# Startracker_Mainboard.net
KiCad netlist of a schematic drawn in Altium Designer
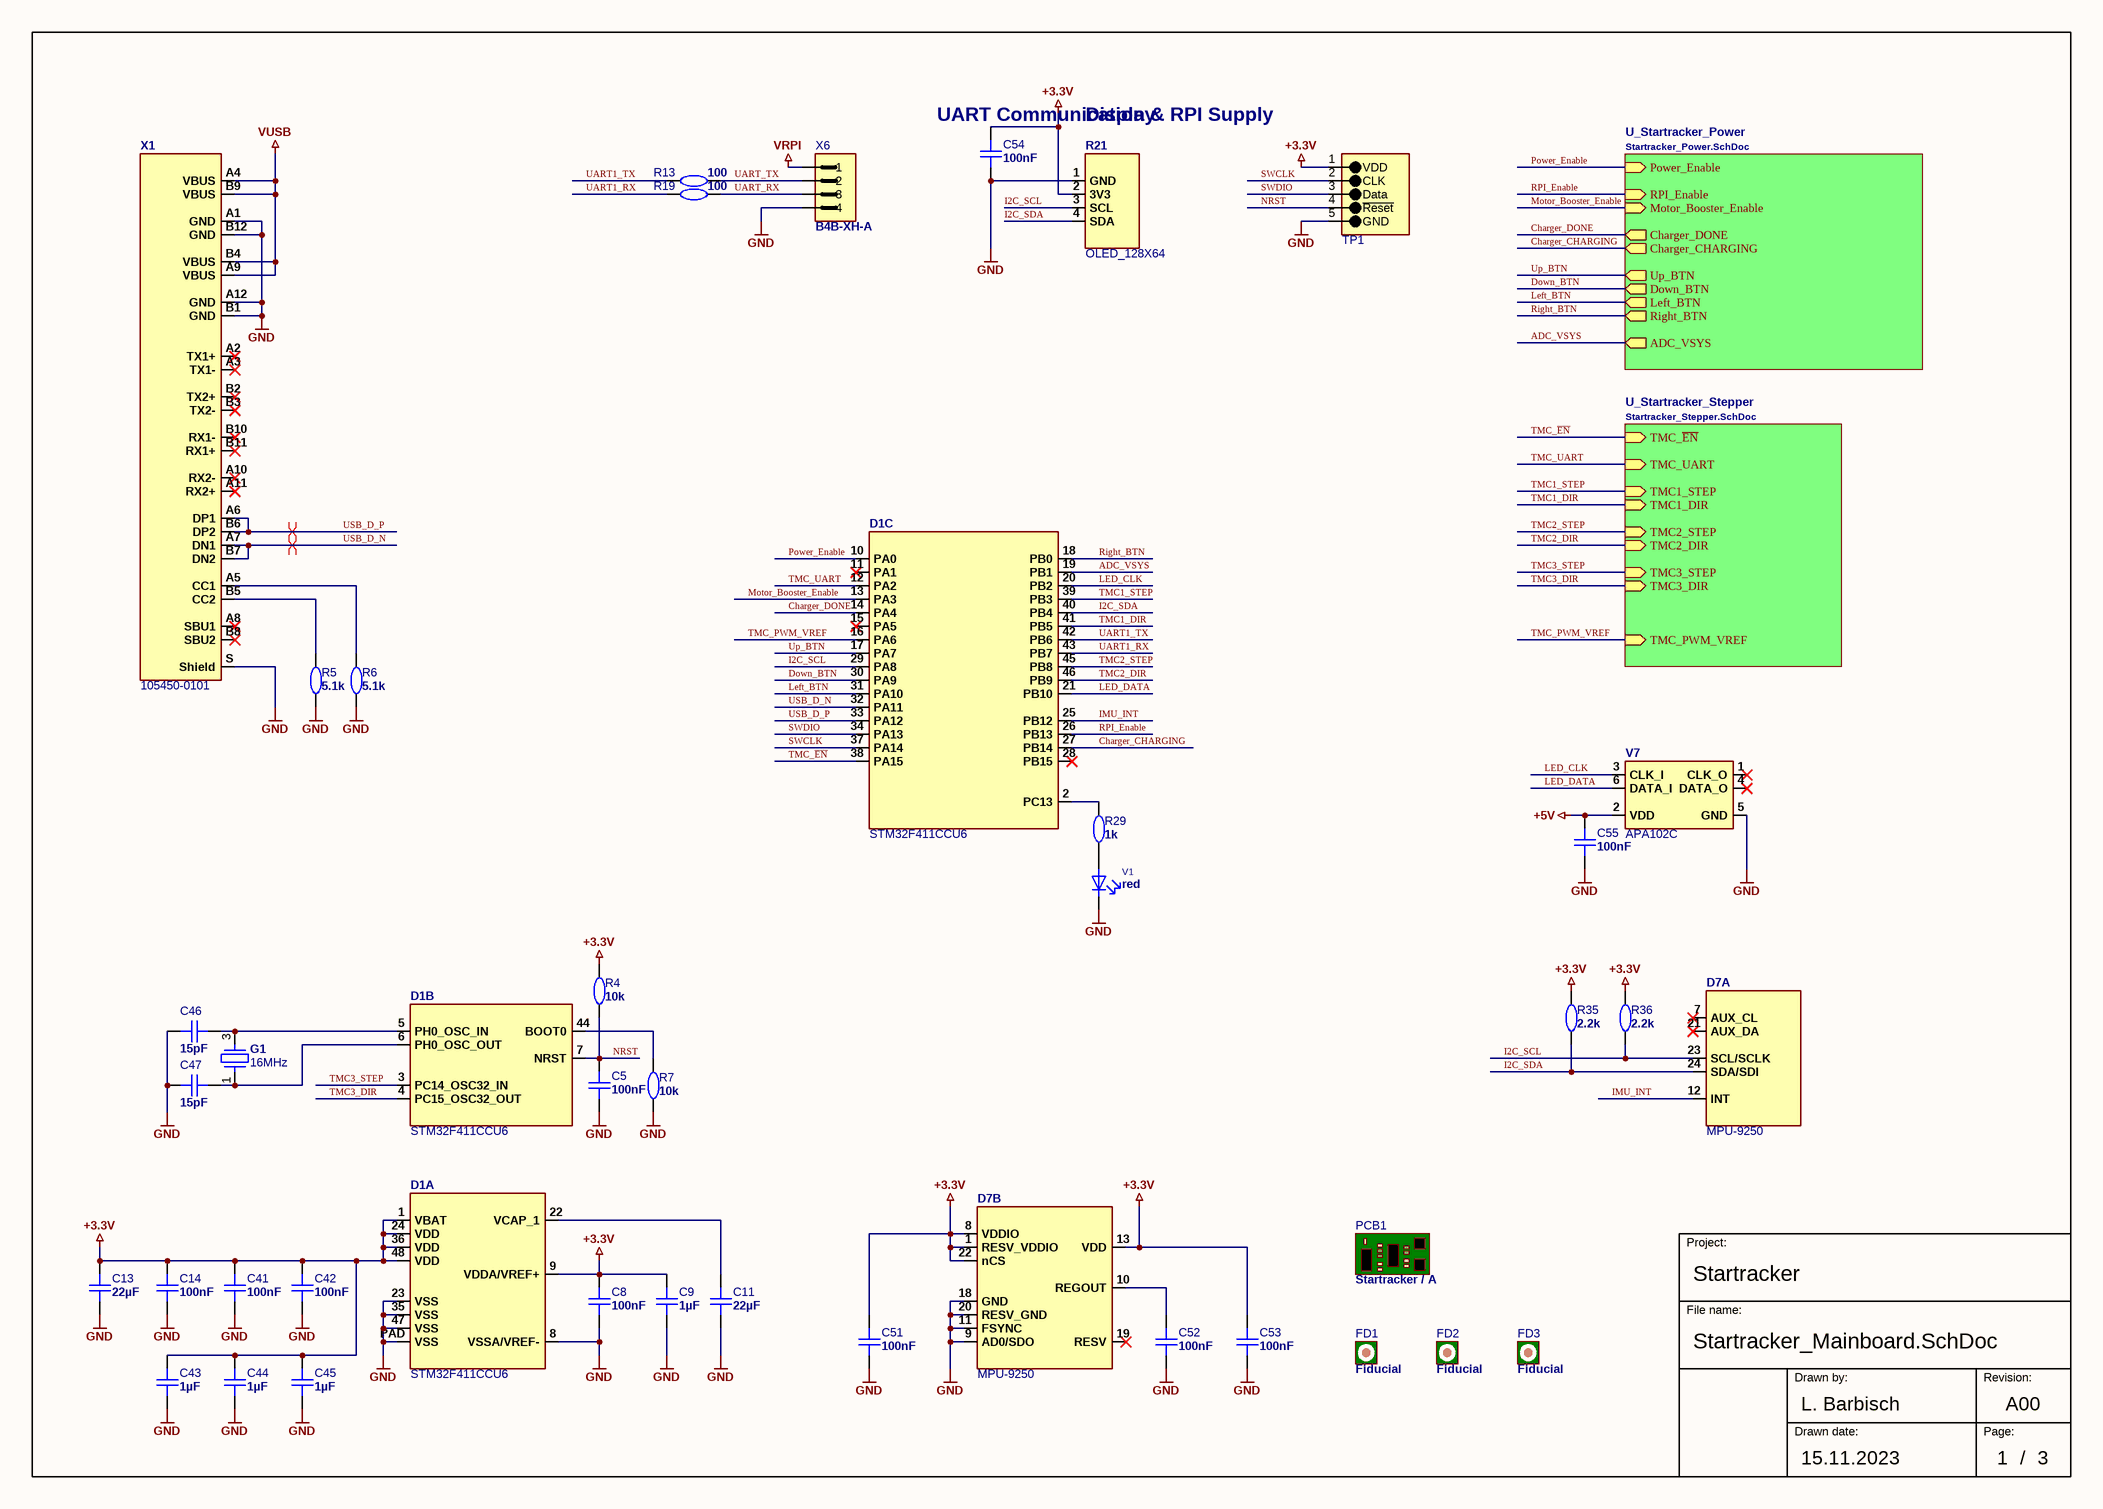
[diagram p0: Startracker_Mainboard.SchDoc]

(export (version "E")
  (design (tool "Eeschema 10.0.6"))
  (components
    (comp (ref "C5")
      (value "100nF")
      (footprint "C-0603_1608_095_L_RF")
      (description "Cap Cer SMD 100n 50V 10% 0603 X7R")
      (fields
        (field (name "MANUFACTURER") "KEMET")
        (field (name "MANUFACTURER PART NUMBER") "C0603C104K5RAC")
        (field (name "USER") "epph")
      )
      (libsource (lib "GPV Switzerland SA") (part "CAP"))
    )
    (comp (ref "C8")
      (value "100nF")
      (footprint "C-0603_1608_095_L_RF")
      (description "Cap Cer SMD 100n 50V 10% 0603 X7R")
      (fields
        (field (name "MANUFACTURER") "KEMET")
        (field (name "MANUFACTURER PART NUMBER") "C0603C104K5RAC")
        (field (name "USER") "epph")
      )
      (libsource (lib "GPV Switzerland SA") (part "CAP"))
    )
    (comp (ref "C9")
      (value "1µF")
      (footprint "C-0603_1608_095_L_RF")
      (description "Cap Cer SMD 1u 16V 10% 0603 X7R")
      (fields
        (field (name "MANUFACTURER PART NUMBER") "0603YC105KAT*")
        (field (name "MANUFACTURER") "AVX")
        (field (name "USER") "zupa")
      )
      (libsource (lib "GPV Switzerland SA") (part "CAP"))
    )
    (comp (ref "C11")
      (value "22µF")
      (footprint "C-0603_1608_110_L_RF")
      (description "Cap Cer SMD 22u 6.3V 20% 0603 X5R")
      (fields
        (field (name "MANUFACTURER PART NUMBER") "C1608X5R0J226M080AC")
        (field (name "MANUFACTURER") "TDK")
        (field (name "USER") "zupa")
      )
      (libsource (lib "GPV Switzerland SA") (part "CAP"))
    )
    (comp (ref "C13")
      (value "22µF")
      (footprint "C-0603_1608_110_L_RF")
      (description "Cap Cer SMD 22u 6.3V 20% 0603 X5R")
      (fields
        (field (name "MANUFACTURER PART NUMBER") "C1608X5R0J226M080AC")
        (field (name "MANUFACTURER") "TDK")
        (field (name "USER") "zupa")
      )
      (libsource (lib "GPV Switzerland SA") (part "CAP"))
    )
    (comp (ref "C14")
      (value "100nF")
      (footprint "C-0603_1608_095_L_RF")
      (description "Cap Cer SMD 100n 50V 10% 0603 X7R")
      (fields
        (field (name "MANUFACTURER") "KEMET")
        (field (name "MANUFACTURER PART NUMBER") "C0603C104K5RAC")
        (field (name "USER") "epph")
      )
      (libsource (lib "GPV Switzerland SA") (part "CAP"))
    )
    (comp (ref "C41")
      (value "100nF")
      (footprint "C-0603_1608_095_L_RF")
      (description "Cap Cer SMD 100n 50V 10% 0603 X7R")
      (fields
        (field (name "MANUFACTURER") "KEMET")
        (field (name "MANUFACTURER PART NUMBER") "C0603C104K5RAC")
        (field (name "USER") "epph")
      )
      (libsource (lib "GPV Switzerland SA") (part "CAP"))
    )
    (comp (ref "C42")
      (value "100nF")
      (footprint "C-0603_1608_095_L_RF")
      (description "Cap Cer SMD 100n 50V 10% 0603 X7R")
      (fields
        (field (name "MANUFACTURER") "KEMET")
        (field (name "MANUFACTURER PART NUMBER") "C0603C104K5RAC")
        (field (name "USER") "epph")
      )
      (libsource (lib "GPV Switzerland SA") (part "CAP"))
    )
    (comp (ref "C43")
      (value "1µF")
      (footprint "C-0603_1608_095_L_RF")
      (description "Cap Cer SMD 1u 16V 10% 0603 X7R")
      (fields
        (field (name "MANUFACTURER PART NUMBER") "0603YC105KAT*")
        (field (name "MANUFACTURER") "AVX")
        (field (name "USER") "zupa")
      )
      (libsource (lib "GPV Switzerland SA") (part "CAP"))
    )
    (comp (ref "C44")
      (value "1µF")
      (footprint "C-0603_1608_095_L_RF")
      (description "Cap Cer SMD 1u 16V 10% 0603 X7R")
      (fields
        (field (name "MANUFACTURER PART NUMBER") "0603YC105KAT*")
        (field (name "MANUFACTURER") "AVX")
        (field (name "USER") "zupa")
      )
      (libsource (lib "GPV Switzerland SA") (part "CAP"))
    )
    (comp (ref "C45")
      (value "1µF")
      (footprint "C-0603_1608_095_L_RF")
      (description "Cap Cer SMD 1u 16V 10% 0603 X7R")
      (fields
        (field (name "MANUFACTURER PART NUMBER") "0603YC105KAT*")
        (field (name "MANUFACTURER") "AVX")
        (field (name "USER") "zupa")
      )
      (libsource (lib "GPV Switzerland SA") (part "CAP"))
    )
    (comp (ref "C46")
      (value "15pF")
      (footprint "C-0603_1608_095_L_RF")
      (description "Cap Cer SMD 15p 50V 5% 0603 C0G")
      (fields
        (field (name "MANUFACTURER") "AVX")
        (field (name "MANUFACTURER PART NUMBER") "06035A150JAT*")
        (field (name "USER") "zupa")
      )
      (libsource (lib "GPV Switzerland SA") (part "CAP"))
    )
    (comp (ref "C47")
      (value "15pF")
      (footprint "C-0603_1608_095_L_RF")
      (description "Cap Cer SMD 15p 50V 5% 0603 C0G")
      (fields
        (field (name "MANUFACTURER") "AVX")
        (field (name "MANUFACTURER PART NUMBER") "06035A150JAT*")
        (field (name "USER") "zupa")
      )
      (libsource (lib "GPV Switzerland SA") (part "CAP"))
    )
    (comp (ref "C51")
      (value "100nF")
      (footprint "C-0603_1608_095_L_RF")
      (description "Cap Cer SMD 100n 50V 10% 0603 X7R")
      (fields
        (field (name "MANUFACTURER") "KEMET")
        (field (name "MANUFACTURER PART NUMBER") "C0603C104K5RAC")
        (field (name "USER") "epph")
      )
      (libsource (lib "GPV Switzerland SA") (part "CAP"))
    )
    (comp (ref "C52")
      (value "100nF")
      (footprint "C-0603_1608_095_L_RF")
      (description "Cap Cer SMD 100n 50V 10% 0603 X7R")
      (fields
        (field (name "MANUFACTURER") "KEMET")
        (field (name "MANUFACTURER PART NUMBER") "C0603C104K5RAC")
        (field (name "USER") "epph")
      )
      (libsource (lib "GPV Switzerland SA") (part "CAP"))
    )
    (comp (ref "C53")
      (value "100nF")
      (footprint "C-0603_1608_095_L_RF")
      (description "Cap Cer SMD 100n 50V 10% 0603 X7R")
      (fields
        (field (name "MANUFACTURER") "KEMET")
        (field (name "MANUFACTURER PART NUMBER") "C0603C104K5RAC")
        (field (name "USER") "epph")
      )
      (libsource (lib "GPV Switzerland SA") (part "CAP"))
    )
    (comp (ref "C54")
      (value "100nF")
      (footprint "C-0603_1608_095_L_RF")
      (description "Cap Cer SMD 100n 50V 10% 0603 X7R")
      (fields
        (field (name "MANUFACTURER") "KEMET")
        (field (name "MANUFACTURER PART NUMBER") "C0603C104K5RAC")
        (field (name "USER") "epph")
      )
      (libsource (lib "GPV Switzerland SA") (part "CAP"))
    )
    (comp (ref "C55")
      (value "100nF")
      (footprint "C-0603_1608_095_L_RF")
      (description "Cap Cer SMD 100n 50V 10% 0603 X7R")
      (fields
        (field (name "MANUFACTURER") "KEMET")
        (field (name "MANUFACTURER PART NUMBER") "C0603C104K5RAC")
        (field (name "USER") "epph")
      )
      (libsource (lib "GPV Switzerland SA") (part "CAP"))
    )
    (comp (ref "D1")
      (value "STM32F411CCU6")
      (footprint "UFQFPN48_N_RF")
      (description "IC MCU Cortex-M4 256k Flash 128k RAM")
      (fields (field (name "MANUFACTURER") "ST Microelectronics"))
      (libsource (lib "Global Library") (part "STM32F411CCU6"))
    )
    (comp (ref "D7")
      (value "MPU-9250")
      (footprint "QFN24_N_RF")
      (description "IC IMU 9-Axis Attitude Sensor")
      (fields (field (name "MANUFACTURER") "InvenSense"))
      (libsource (lib "Global Library") (part "MPU-9250"))
    )
    (comp (ref "FD1")
      (value "Fiducial")
      (footprint "Fiducial_1.0mm")
      (description "Fiducial Mark")
      (fields (field (name "USER") "balu"))
      (libsource (lib "GPV Switzerland SA") (part "Fiducial"))
    )
    (comp (ref "FD2")
      (value "Fiducial")
      (footprint "Fiducial_1.0mm")
      (description "Fiducial Mark")
      (fields (field (name "USER") "balu"))
      (libsource (lib "GPV Switzerland SA") (part "Fiducial"))
    )
    (comp (ref "FD3")
      (value "Fiducial")
      (footprint "Fiducial_1.0mm")
      (description "Fiducial Mark")
      (fields (field (name "USER") "balu"))
      (libsource (lib "GPV Switzerland SA") (part "Fiducial"))
    )
    (comp (ref "G1")
      (value "16MHz")
      (footprint "G_3225_N_RF")
      (description "Crystal Oscillator 16MHz 10pF ±10ppm LCSC C112972")
      (fields
        (field (name "MANUFACTURER") "Yangwing Tech")
        (field (name "MANUFACTURER PART NUMBER") "X322516MMB4SI")
      )
      (libsource (lib "Global Library") (part "X322516MMB4SI"))
    )
    (comp (ref "PCB1")
      (value "/")
      (footprint "Dummy_PCB-Parameter_SM")
      (description "<PCB DesignName Revision>")
      (fields (field (name "Comment") "PCB_Dummy") (field (name "USER") "balu"))
      (libsource (lib "GPV Switzerland SA") (part "PCB"))
    )
    (comp (ref "R4")
      (value "10k")
      (footprint "R-0603_1608_050_L_RF")
      (description "Res SMD 10k 1% 0.1W 0603")
      (fields
        (field (name "MANUFACTURER") "YAGEO")
        (field (name "MANUFACTURER PART NUMBER") "RC0603FR-0710KL")
        (field (name "USER") "zupa")
      )
      (libsource (lib "GPV Switzerland SA") (part "RES"))
    )
    (comp (ref "R5")
      (value "5.1k")
      (footprint "R-0603_1608_050_L_RF")
      (description "Res SMD 5k1 1% 0.1W 0603")
      (fields
        (field (name "MANUFACTURER PART NUMBER") "RC0603FR-075K1L")
        (field (name "MANUFACTURER") "YAGEO")
        (field (name "USER") "napa")
      )
      (libsource (lib "GPV Switzerland SA") (part "RES"))
    )
    (comp (ref "R6")
      (value "5.1k")
      (footprint "R-0603_1608_050_L_RF")
      (description "Res SMD 5k1 1% 0.1W 0603")
      (fields
        (field (name "MANUFACTURER PART NUMBER") "RC0603FR-075K1L")
        (field (name "MANUFACTURER") "YAGEO")
        (field (name "USER") "napa")
      )
      (libsource (lib "GPV Switzerland SA") (part "RES"))
    )
    (comp (ref "R7")
      (value "10k")
      (footprint "R-0603_1608_050_L_RF")
      (description "Res SMD 10k 1% 0.1W 0603")
      (fields
        (field (name "MANUFACTURER") "YAGEO")
        (field (name "MANUFACTURER PART NUMBER") "RC0603FR-0710KL")
        (field (name "USER") "zupa")
      )
      (libsource (lib "GPV Switzerland SA") (part "RES"))
    )
    (comp (ref "R13")
      (value "100")
      (footprint "R-0603_1608_050_L_RF")
      (description "Res SMD 100R 1% 0.1W 0603")
      (fields
        (field (name "MANUFACTURER") "YAGEO")
        (field (name "MANUFACTURER PART NUMBER") "RC0603FR-07100RL")
        (field (name "USER") "zupa")
      )
      (libsource (lib "GPV Switzerland SA") (part "RES"))
    )
    (comp (ref "R19")
      (value "100")
      (footprint "R-0603_1608_050_L_RF")
      (description "Res SMD 100R 1% 0.1W 0603")
      (fields
        (field (name "MANUFACTURER") "YAGEO")
        (field (name "MANUFACTURER PART NUMBER") "RC0603FR-07100RL")
        (field (name "USER") "zupa")
      )
      (libsource (lib "GPV Switzerland SA") (part "RES"))
    )
    (comp (ref "R21")
      (value "OLED_128X64")
      (footprint "OLED_0.96")
      (description "OLED Display I2C 128X64 0.96\"")
      (libsource (lib "Global Library") (part "Display_0.96"))
    )
    (comp (ref "R29")
      (value "1k")
      (footprint "R-0603_1608_050_L_RF")
      (description "Res SMD 1k 1% 0.1W 0603")
      (fields
        (field (name "MANUFACTURER") "YAGEO")
        (field (name "MANUFACTURER PART NUMBER") "RC0603FR-071KL")
        (field (name "USER") "zupa")
      )
      (libsource (lib "GPV Switzerland SA") (part "RES"))
    )
    (comp (ref "R35")
      (value "2.2k")
      (footprint "R-0603_1608_050_L_RF")
      (description "Res SMD 2k2 1% 0.1W 0603")
      (fields
        (field (name "MANUFACTURER") "YAGEO")
        (field (name "MANUFACTURER PART NUMBER") "RC0603FR-072K2L")
        (field (name "USER") "zupa")
      )
      (libsource (lib "GPV Switzerland SA") (part "RES"))
    )
    (comp (ref "R36")
      (value "2.2k")
      (footprint "R-0603_1608_050_L_RF")
      (description "Res SMD 2k2 1% 0.1W 0603")
      (fields
        (field (name "MANUFACTURER") "YAGEO")
        (field (name "MANUFACTURER PART NUMBER") "RC0603FR-072K2L")
        (field (name "USER") "zupa")
      )
      (libsource (lib "GPV Switzerland SA") (part "RES"))
    )
    (comp (ref "TP1")
      (value "Programming Interface 5P")
      (footprint "TP_ProgrammingInterface_5P_A")
      (fields (field (name "USER") "zupa"))
      (libsource (lib "GPV Switzerland SA") (part "Programming_Interface-5P"))
    )
    (comp (ref "V1")
      (value "red")
      (footprint "LED-0603_1608_Red_L_RF")
      (description "LED RED LTST-C190KDKT-10A 0603")
      (fields
        (field (name "MANUFACTURER PART NUMBER") "LTST-C190KDKT-10A")
        (field (name "MANUFACTURER") "Lite-On Inc")
        (field (name "USER") "epph")
      )
      (libsource (lib "GPV Switzerland SA") (part "LED"))
    )
    (comp (ref "V7")
      (value "APA102C")
      (footprint "V_2020_P6_N_RF")
      (description "RGB LED SPI Interface")
      (fields
        (field (name "MANUFACTURER") "APA Electronic CO")
        (field (name "MANUFACTURER PART NUMBER") "APA-102-2020-256-8A")
      )
      (libsource (lib "Global Library") (part "APA102C"))
    )
    (comp (ref "X1")
      (value "105450-0101")
      (footprint "105450-0101")
      (description "CONN USB-C 16pin")
      (fields (field (name "MANUFACTURER") "Molex"))
      (libsource (lib "Global Library") (part "105450-0101"))
    )
    (comp (ref "X6")
      (value "B4B-XH-A")
      (footprint "X-0124X0057-R_M04_P0250_JST_B4B-XH-A")
      (description "CONN HEADER  4POS_JST_B4B-XH")
      (fields
        (field (name "MANUFACTURER") "JST")
        (field (name "Comment") "CONN HEADER XH 4POS THT")
        (field (name "USER") "balu")
      )
      (libsource (lib "GPV Switzerland SA") (part "Connector-4P"))
    )
  )
  (nets
    (net (code "1") (name "+3.3V") (class "Default")
      (node (ref "C13") (pin "2") (pinfunction "2_2") (pintype "passive"))
      (node (ref "C14") (pin "1") (pinfunction "1_1") (pintype "passive"))
      (node (ref "C41") (pin "1") (pinfunction "1_1") (pintype "passive"))
      (node (ref "C42") (pin "1") (pinfunction "1_1") (pintype "passive"))
      (node (ref "C43") (pin "2") (pinfunction "2_2") (pintype "passive"))
      (node (ref "C44") (pin "2") (pinfunction "2_2") (pintype "passive"))
      (node (ref "C45") (pin "2") (pinfunction "2_2") (pintype "passive"))
      (node (ref "C51") (pin "1") (pinfunction "1_1") (pintype "passive"))
      (node (ref "C53") (pin "1") (pinfunction "1_1") (pintype "passive"))
      (node (ref "C54") (pin "1") (pinfunction "1_1") (pintype "passive"))
      (node (ref "C8") (pin "1") (pinfunction "1_1") (pintype "passive"))
      (node (ref "C9") (pin "2") (pinfunction "2_2") (pintype "passive"))
      (node (ref "D1") (pin "1") (pinfunction "VBAT_1") (pintype "passive"))
      (node (ref "D1") (pin "24") (pinfunction "VDD_24") (pintype "passive"))
      (node (ref "D1") (pin "36") (pinfunction "VDD_36") (pintype "passive"))
      (node (ref "D1") (pin "48") (pinfunction "VDD_48") (pintype "passive"))
      (node (ref "D1") (pin "9") (pinfunction "VDDA/VREF+_9") (pintype "passive"))
      (node (ref "D7") (pin "1") (pinfunction "RESV_VDDIO_1") (pintype "passive"))
      (node (ref "D7") (pin "13") (pinfunction "VDD_13") (pintype "passive"))
      (node (ref "D7") (pin "22") (pinfunction "nCS_22") (pintype "passive"))
      (node (ref "D7") (pin "8") (pinfunction "VDDIO_8") (pintype "passive"))
      (node (ref "R21") (pin "2") (pinfunction "3V3_2") (pintype "passive"))
      (node (ref "R35") (pin "1") (pinfunction "1_1") (pintype "passive"))
      (node (ref "R36") (pin "1") (pinfunction "1_1") (pintype "passive"))
      (node (ref "R4") (pin "2") (pinfunction "2_2") (pintype "passive"))
      (node (ref "TP1") (pin "1") (pinfunction "VDD_1") (pintype "passive"))
    )
    (net (code "2") (name "+5V") (class "Default")
      (node (ref "C55") (pin "1") (pinfunction "1_1") (pintype "passive"))
      (node (ref "V7") (pin "2") (pinfunction "VDD_2") (pintype "passive"))
    )
    (net (code "3") (name "/ADC_VSYS") (class "Default")
      (node (ref "D1") (pin "19") (pinfunction "PB1_19") (pintype "passive"))
    )
    (net (code "4") (name "/Charger_CHARGING") (class "Default")
      (node (ref "D1") (pin "27") (pinfunction "PB14_27") (pintype "passive"))
    )
    (net (code "5") (name "/Charger_DONE") (class "Default")
      (node (ref "D1") (pin "14") (pinfunction "PA4_14") (pintype "passive"))
    )
    (net (code "6") (name "/Down_BTN") (class "Default")
      (node (ref "D1") (pin "30") (pinfunction "PA9_30") (pintype "passive"))
    )
    (net (code "7") (name "/I2C_SCL") (class "Default")
      (node (ref "D1") (pin "29") (pinfunction "PA8_29") (pintype "passive"))
      (node (ref "D7") (pin "23") (pinfunction "SCL/SCLK_23") (pintype "passive"))
      (node (ref "R21") (pin "3") (pinfunction "SCL_3") (pintype "passive"))
      (node (ref "R36") (pin "2") (pinfunction "2_2") (pintype "passive"))
    )
    (net (code "8") (name "/I2C_SDA") (class "Default")
      (node (ref "D1") (pin "40") (pinfunction "PB4_40") (pintype "passive"))
      (node (ref "D7") (pin "24") (pinfunction "SDA/SDI_24") (pintype "passive"))
      (node (ref "R21") (pin "4") (pinfunction "SDA_4") (pintype "passive"))
      (node (ref "R35") (pin "2") (pinfunction "2_2") (pintype "passive"))
    )
    (net (code "9") (name "/IMU_INT") (class "Default")
      (node (ref "D1") (pin "25") (pinfunction "PB12_25") (pintype "passive"))
      (node (ref "D7") (pin "12") (pinfunction "INT_12") (pintype "passive"))
    )
    (net (code "10") (name "/LED_CLK") (class "Default")
      (node (ref "D1") (pin "20") (pinfunction "PB2_20") (pintype "passive"))
      (node (ref "V7") (pin "3") (pinfunction "CLK_I_3") (pintype "passive"))
    )
    (net (code "11") (name "/LED_DATA") (class "Default")
      (node (ref "D1") (pin "21") (pinfunction "PB10_21") (pintype "passive"))
      (node (ref "V7") (pin "6") (pinfunction "DATA_I_6") (pintype "passive"))
    )
    (net (code "12") (name "/Left_BTN") (class "Default")
      (node (ref "D1") (pin "31") (pinfunction "PA10_31") (pintype "passive"))
    )
    (net (code "13") (name "/Motor_Booster_Enable") (class "Default")
      (node (ref "D1") (pin "13") (pinfunction "PA3_13") (pintype "passive"))
    )
    (net (code "14") (name "/NRST") (class "Default")
      (node (ref "C5") (pin "1") (pinfunction "1_1") (pintype "passive"))
      (node (ref "D1") (pin "7") (pinfunction "NRST_7") (pintype "passive"))
      (node (ref "R4") (pin "1") (pinfunction "1_1") (pintype "passive"))
      (node (ref "TP1") (pin "4") (pinfunction "Reset_4") (pintype "passive"))
    )
    (net (code "15") (name "/Power_Enable") (class "Default")
      (node (ref "D1") (pin "10") (pinfunction "PA0_10") (pintype "passive"))
    )
    (net (code "16") (name "/RPI_Enable") (class "Default")
      (node (ref "D1") (pin "26") (pinfunction "PB13_26") (pintype "passive"))
    )
    (net (code "17") (name "/Right_BTN") (class "Default")
      (node (ref "D1") (pin "18") (pinfunction "PB0_18") (pintype "passive"))
    )
    (net (code "18") (name "/SWCLK") (class "Default")
      (node (ref "D1") (pin "37") (pinfunction "PA14_37") (pintype "passive"))
      (node (ref "TP1") (pin "2") (pinfunction "CLK_2") (pintype "passive"))
    )
    (net (code "19") (name "/SWDIO") (class "Default")
      (node (ref "D1") (pin "34") (pinfunction "PA13_34") (pintype "passive"))
      (node (ref "TP1") (pin "3") (pinfunction "Data_3") (pintype "passive"))
    )
    (net (code "20") (name "/TMC1_DIR") (class "Default")
      (node (ref "D1") (pin "41") (pinfunction "PB5_41") (pintype "passive"))
    )
    (net (code "21") (name "/TMC1_STEP") (class "Default")
      (node (ref "D1") (pin "39") (pinfunction "PB3_39") (pintype "passive"))
    )
    (net (code "22") (name "/TMC2_DIR") (class "Default")
      (node (ref "D1") (pin "46") (pinfunction "PB9_46") (pintype "passive"))
    )
    (net (code "23") (name "/TMC2_STEP") (class "Default")
      (node (ref "D1") (pin "45") (pinfunction "PB8_45") (pintype "passive"))
    )
    (net (code "24") (name "/TMC3_DIR") (class "Default")
      (node (ref "D1") (pin "4") (pinfunction "PC15_OSC32_OUT_4") (pintype "passive"))
    )
    (net (code "25") (name "/TMC3_STEP") (class "Default")
      (node (ref "D1") (pin "3") (pinfunction "PC14_OSC32_IN_3") (pintype "passive"))
    )
    (net (code "26") (name "/TMC_PWM_VREF") (class "Default")
      (node (ref "D1") (pin "16") (pinfunction "PA6_16") (pintype "passive"))
    )
    (net (code "27") (name "/TMC_UART") (class "Default")
      (node (ref "D1") (pin "12") (pinfunction "PA2_12") (pintype "passive"))
    )
    (net (code "28") (name "/TMC_~{EN}") (class "Default")
      (node (ref "D1") (pin "38") (pinfunction "PA15_38") (pintype "passive"))
    )
    (net (code "29") (name "/UART1_RX") (class "Default")
      (node (ref "D1") (pin "43") (pinfunction "PB7_43") (pintype "passive"))
      (node (ref "R19") (pin "1") (pinfunction "1_1") (pintype "passive"))
    )
    (net (code "30") (name "/UART1_TX") (class "Default")
      (node (ref "D1") (pin "42") (pinfunction "PB6_42") (pintype "passive"))
      (node (ref "R13") (pin "1") (pinfunction "1_1") (pintype "passive"))
    )
    (net (code "31") (name "/UART_RX") (class "Default")
      (node (ref "R19") (pin "2") (pinfunction "2_2") (pintype "passive"))
      (node (ref "X6") (pin "3") (pinfunction "3_3") (pintype "passive"))
    )
    (net (code "32") (name "/UART_TX") (class "Default")
      (node (ref "R13") (pin "2") (pinfunction "2_2") (pintype "passive"))
      (node (ref "X6") (pin "2") (pinfunction "2_2") (pintype "passive"))
    )
    (net (code "33") (name "/USB_D_N") (class "Default")
      (node (ref "D1") (pin "32") (pinfunction "PA11_32") (pintype "passive"))
      (node (ref "X1") (pin "A7") (pinfunction "DN1_A7") (pintype "passive"))
      (node (ref "X1") (pin "B7") (pinfunction "DN2_B7") (pintype "passive"))
    )
    (net (code "34") (name "/USB_D_P") (class "Default")
      (node (ref "D1") (pin "33") (pinfunction "PA12_33") (pintype "passive"))
      (node (ref "X1") (pin "A6") (pinfunction "DP1_A6") (pintype "passive"))
      (node (ref "X1") (pin "B6") (pinfunction "DP2_B6") (pintype "passive"))
    )
    (net (code "35") (name "/Up_BTN") (class "Default")
      (node (ref "D1") (pin "17") (pinfunction "PA7_17") (pintype "passive"))
    )
    (net (code "36") (name "GND") (class "Default")
      (node (ref "C11") (pin "1") (pinfunction "1_1") (pintype "passive"))
      (node (ref "C13") (pin "1") (pinfunction "1_1") (pintype "passive"))
      (node (ref "C14") (pin "2") (pinfunction "2_2") (pintype "passive"))
      (node (ref "C41") (pin "2") (pinfunction "2_2") (pintype "passive"))
      (node (ref "C42") (pin "2") (pinfunction "2_2") (pintype "passive"))
      (node (ref "C43") (pin "1") (pinfunction "1_1") (pintype "passive"))
      (node (ref "C44") (pin "1") (pinfunction "1_1") (pintype "passive"))
      (node (ref "C45") (pin "1") (pinfunction "1_1") (pintype "passive"))
      (node (ref "C46") (pin "2") (pinfunction "2_2") (pintype "passive"))
      (node (ref "C47") (pin "2") (pinfunction "2_2") (pintype "passive"))
      (node (ref "C5") (pin "2") (pinfunction "2_2") (pintype "passive"))
      (node (ref "C51") (pin "2") (pinfunction "2_2") (pintype "passive"))
      (node (ref "C52") (pin "2") (pinfunction "2_2") (pintype "passive"))
      (node (ref "C53") (pin "2") (pinfunction "2_2") (pintype "passive"))
      (node (ref "C54") (pin "2") (pinfunction "2_2") (pintype "passive"))
      (node (ref "C55") (pin "2") (pinfunction "2_2") (pintype "passive"))
      (node (ref "C8") (pin "2") (pinfunction "2_2") (pintype "passive"))
      (node (ref "C9") (pin "1") (pinfunction "1_1") (pintype "passive"))
      (node (ref "D1") (pin "23") (pinfunction "VSS_23") (pintype "passive"))
      (node (ref "D1") (pin "35") (pinfunction "VSS_35") (pintype "passive"))
      (node (ref "D1") (pin "47") (pinfunction "VSS_47") (pintype "passive"))
      (node (ref "D1") (pin "8") (pinfunction "VSSA/VREF-_8") (pintype "passive"))
      (node (ref "D1") (pin "PAD") (pinfunction "VSS_PAD") (pintype "passive"))
      (node (ref "D7") (pin "11") (pinfunction "FSYNC_11") (pintype "passive"))
      (node (ref "D7") (pin "18") (pinfunction "GND_18") (pintype "passive"))
      (node (ref "D7") (pin "20") (pinfunction "RESV_GND_20") (pintype "passive"))
      (node (ref "D7") (pin "9") (pinfunction "AD0/SDO_9") (pintype "passive"))
      (node (ref "R21") (pin "1") (pinfunction "GND_1") (pintype "passive"))
      (node (ref "R5") (pin "1") (pinfunction "1_1") (pintype "passive"))
      (node (ref "R6") (pin "1") (pinfunction "1_1") (pintype "passive"))
      (node (ref "R7") (pin "1") (pinfunction "1_1") (pintype "passive"))
      (node (ref "TP1") (pin "5") (pinfunction "GND_5") (pintype "passive"))
      (node (ref "V1") (pin "2") (pinfunction "2_2") (pintype "passive"))
      (node (ref "V7") (pin "5") (pinfunction "GND_5") (pintype "passive"))
      (node (ref "X1") (pin "A1") (pinfunction "GND_A1") (pintype "passive"))
      (node (ref "X1") (pin "A12") (pinfunction "GND_A12") (pintype "passive"))
      (node (ref "X1") (pin "B1") (pinfunction "GND_B1") (pintype "passive"))
      (node (ref "X1") (pin "B12") (pinfunction "GND_B12") (pintype "passive"))
      (node (ref "X1") (pin "S") (pinfunction "Shield_S") (pintype "passive"))
      (node (ref "X6") (pin "4") (pinfunction "4_4") (pintype "passive"))
    )
    (net (code "37") (name "Net-(D1A-VCAP_1)") (class "Default")
      (node (ref "C11") (pin "2") (pinfunction "2_2") (pintype "passive"))
      (node (ref "D1") (pin "22") (pinfunction "VCAP_1_22") (pintype "passive"))
    )
    (net (code "38") (name "Net-(D1B-BOOT0)") (class "Default")
      (node (ref "D1") (pin "44") (pinfunction "BOOT0_44") (pintype "passive"))
      (node (ref "R7") (pin "2") (pinfunction "2_2") (pintype "passive"))
    )
    (net (code "39") (name "Net-(D1B-PH0_OSC_IN)") (class "Default")
      (node (ref "C46") (pin "1") (pinfunction "1_1") (pintype "passive"))
      (node (ref "D1") (pin "5") (pinfunction "PH0_OSC_IN_5") (pintype "passive"))
      (node (ref "G1") (pin "3") (pintype "passive"))
    )
    (net (code "40") (name "Net-(D1B-PH0_OSC_OUT)") (class "Default")
      (node (ref "C47") (pin "1") (pinfunction "1_1") (pintype "passive"))
      (node (ref "D1") (pin "6") (pinfunction "PH0_OSC_OUT_6") (pintype "passive"))
      (node (ref "G1") (pin "1") (pintype "passive"))
    )
    (net (code "41") (name "Net-(D1C-PC13)") (class "Default")
      (node (ref "D1") (pin "2") (pinfunction "PC13_2") (pintype "passive"))
      (node (ref "R29") (pin "2") (pinfunction "2_2") (pintype "passive"))
    )
    (net (code "42") (name "Net-(D7B-REGOUT)") (class "Default")
      (node (ref "C52") (pin "1") (pinfunction "1_1") (pintype "passive"))
      (node (ref "D7") (pin "10") (pinfunction "REGOUT_10") (pintype "passive"))
    )
    (net (code "43") (name "Net-(R29-Pad1)") (class "Default")
      (node (ref "R29") (pin "1") (pinfunction "1_1") (pintype "passive"))
      (node (ref "V1") (pin "1") (pinfunction "1_1") (pintype "passive"))
    )
    (net (code "44") (name "Net-(X1-CC1)") (class "Default")
      (node (ref "R6") (pin "2") (pinfunction "2_2") (pintype "passive"))
      (node (ref "X1") (pin "A5") (pinfunction "CC1_A5") (pintype "passive"))
    )
    (net (code "45") (name "Net-(X1-CC2)") (class "Default")
      (node (ref "R5") (pin "2") (pinfunction "2_2") (pintype "passive"))
      (node (ref "X1") (pin "B5") (pinfunction "CC2_B5") (pintype "passive"))
    )
    (net (code "46") (name "VRPI") (class "Default")
      (node (ref "X6") (pin "1") (pinfunction "1_1") (pintype "passive"))
    )
    (net (code "47") (name "VUSB") (class "Default")
      (node (ref "X1") (pin "A4") (pinfunction "VBUS_A4") (pintype "passive"))
      (node (ref "X1") (pin "A9") (pinfunction "VBUS_A9") (pintype "passive"))
      (node (ref "X1") (pin "B4") (pinfunction "VBUS_B4") (pintype "passive"))
      (node (ref "X1") (pin "B9") (pinfunction "VBUS_B9") (pintype "passive"))
    )
    (net (code "48") (name "unconnected-(D1C-PA1-Pad11)") (class "Default")
      (node (ref "D1") (pin "11") (pinfunction "PA1_11") (pintype "passive+no_connect"))
    )
    (net (code "49") (name "unconnected-(D1C-PA5-Pad15)") (class "Default")
      (node (ref "D1") (pin "15") (pinfunction "PA5_15") (pintype "passive+no_connect"))
    )
    (net (code "50") (name "unconnected-(D1C-PB15-Pad28)") (class "Default")
      (node (ref "D1") (pin "28") (pinfunction "PB15_28") (pintype "passive+no_connect"))
    )
    (net (code "51") (name "unconnected-(D7A-AUX_CL-Pad7)") (class "Default")
      (node (ref "D7") (pin "7") (pinfunction "AUX_CL_7") (pintype "passive+no_connect"))
    )
    (net (code "52") (name "unconnected-(D7A-AUX_DA-Pad21)") (class "Default")
      (node (ref "D7") (pin "21") (pinfunction "AUX_DA_21") (pintype "passive+no_connect"))
    )
    (net (code "53") (name "unconnected-(D7B-RESV-Pad19)") (class "Default")
      (node (ref "D7") (pin "19") (pinfunction "RESV_19") (pintype "passive+no_connect"))
    )
    (net (code "54") (name "unconnected-(V7-CLK_O-Pad1)") (class "Default")
      (node (ref "V7") (pin "1") (pinfunction "CLK_O_1") (pintype "passive+no_connect"))
    )
    (net (code "55") (name "unconnected-(V7-DATA_O-Pad4)") (class "Default")
      (node (ref "V7") (pin "4") (pinfunction "DATA_O_4") (pintype "passive+no_connect"))
    )
    (net (code "56") (name "unconnected-(X1-RX1+-PadB11)") (class "Default")
      (node (ref "X1") (pin "B11") (pinfunction "RX1+_B11") (pintype "passive+no_connect"))
    )
    (net (code "57") (name "unconnected-(X1-RX1--PadB10)") (class "Default")
      (node (ref "X1") (pin "B10") (pinfunction "RX1-_B10") (pintype "passive+no_connect"))
    )
    (net (code "58") (name "unconnected-(X1-RX2+-PadA11)") (class "Default")
      (node (ref "X1") (pin "A11") (pinfunction "RX2+_A11") (pintype "passive+no_connect"))
    )
    (net (code "59") (name "unconnected-(X1-RX2--PadA10)") (class "Default")
      (node (ref "X1") (pin "A10") (pinfunction "RX2-_A10") (pintype "passive+no_connect"))
    )
    (net (code "60") (name "unconnected-(X1-SBU1-PadA8)") (class "Default")
      (node (ref "X1") (pin "A8") (pinfunction "SBU1_A8") (pintype "passive+no_connect"))
    )
    (net (code "61") (name "unconnected-(X1-SBU2-PadB8)") (class "Default")
      (node (ref "X1") (pin "B8") (pinfunction "SBU2_B8") (pintype "passive+no_connect"))
    )
    (net (code "62") (name "unconnected-(X1-TX1+-PadA2)") (class "Default")
      (node (ref "X1") (pin "A2") (pinfunction "TX1+_A2") (pintype "passive+no_connect"))
    )
    (net (code "63") (name "unconnected-(X1-TX1--PadA3)") (class "Default")
      (node (ref "X1") (pin "A3") (pinfunction "TX1-_A3") (pintype "passive+no_connect"))
    )
    (net (code "64") (name "unconnected-(X1-TX2+-PadB2)") (class "Default")
      (node (ref "X1") (pin "B2") (pinfunction "TX2+_B2") (pintype "passive+no_connect"))
    )
    (net (code "65") (name "unconnected-(X1-TX2--PadB3)") (class "Default")
      (node (ref "X1") (pin "B3") (pinfunction "TX2-_B3") (pintype "passive+no_connect"))
    )
  )
)
